# Analog_Filter.net
KiCad netlist of a schematic drawn in Altium Designer
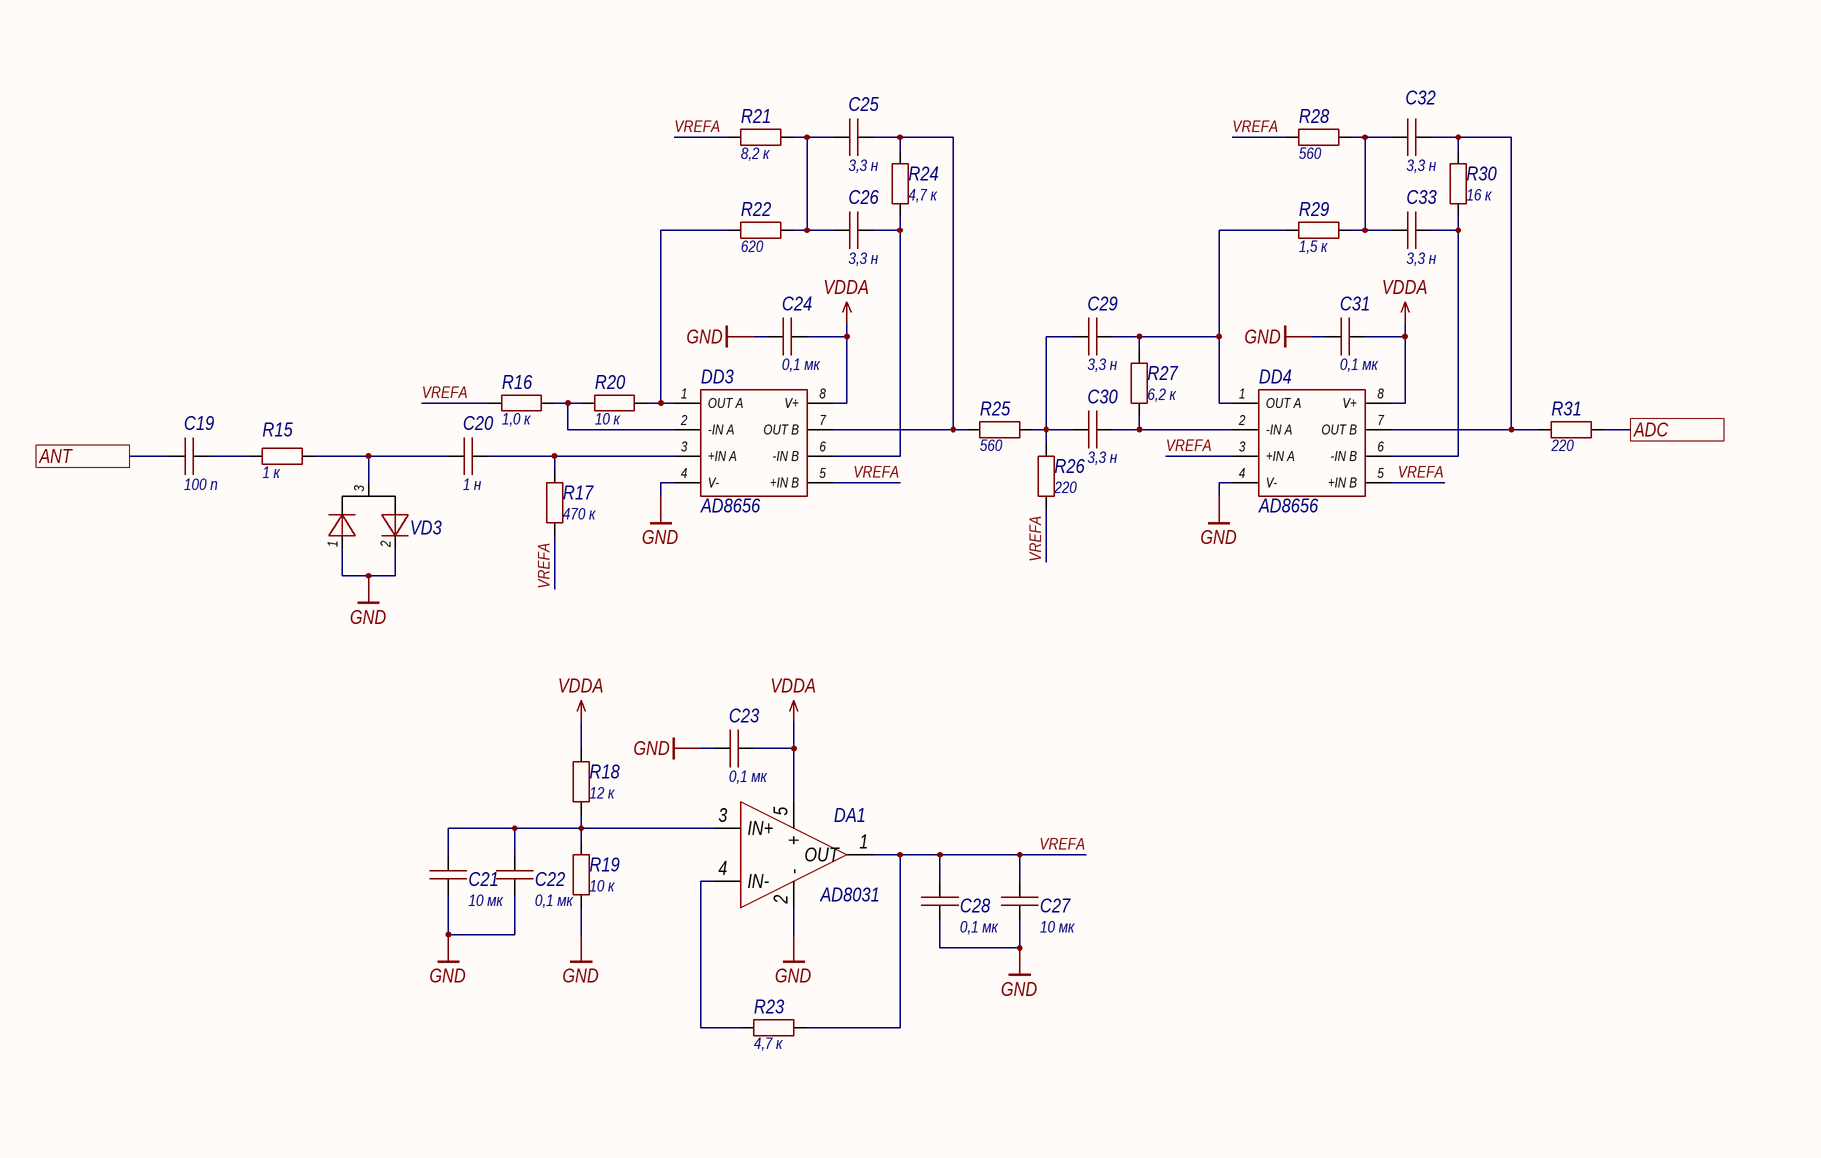
[diagram p0: Analog_Filter.SchDoc, left]
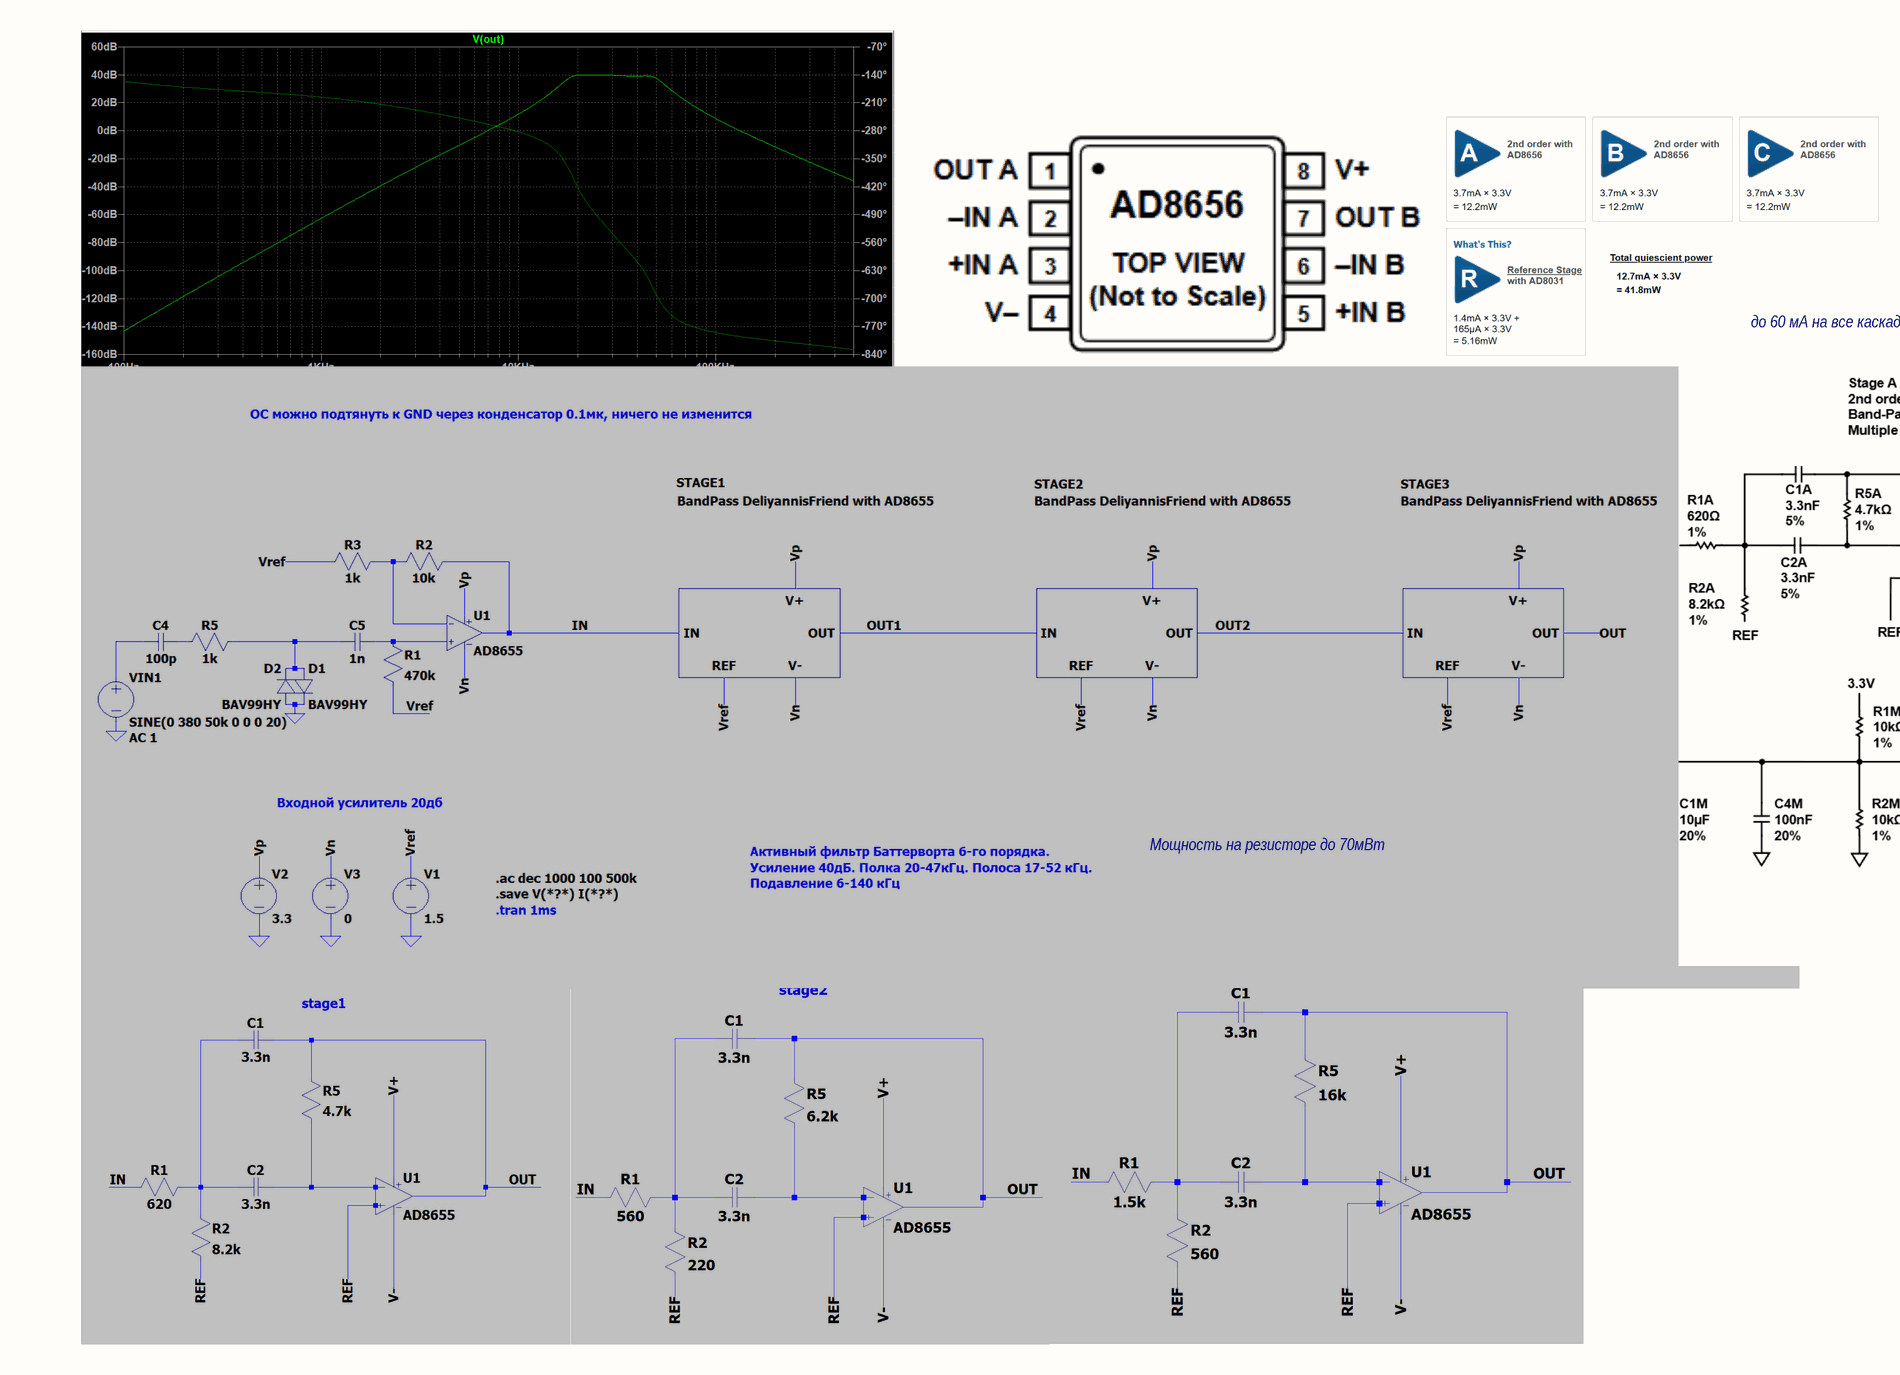
[diagram p1: Analog_Filter.SchDoc, middle]
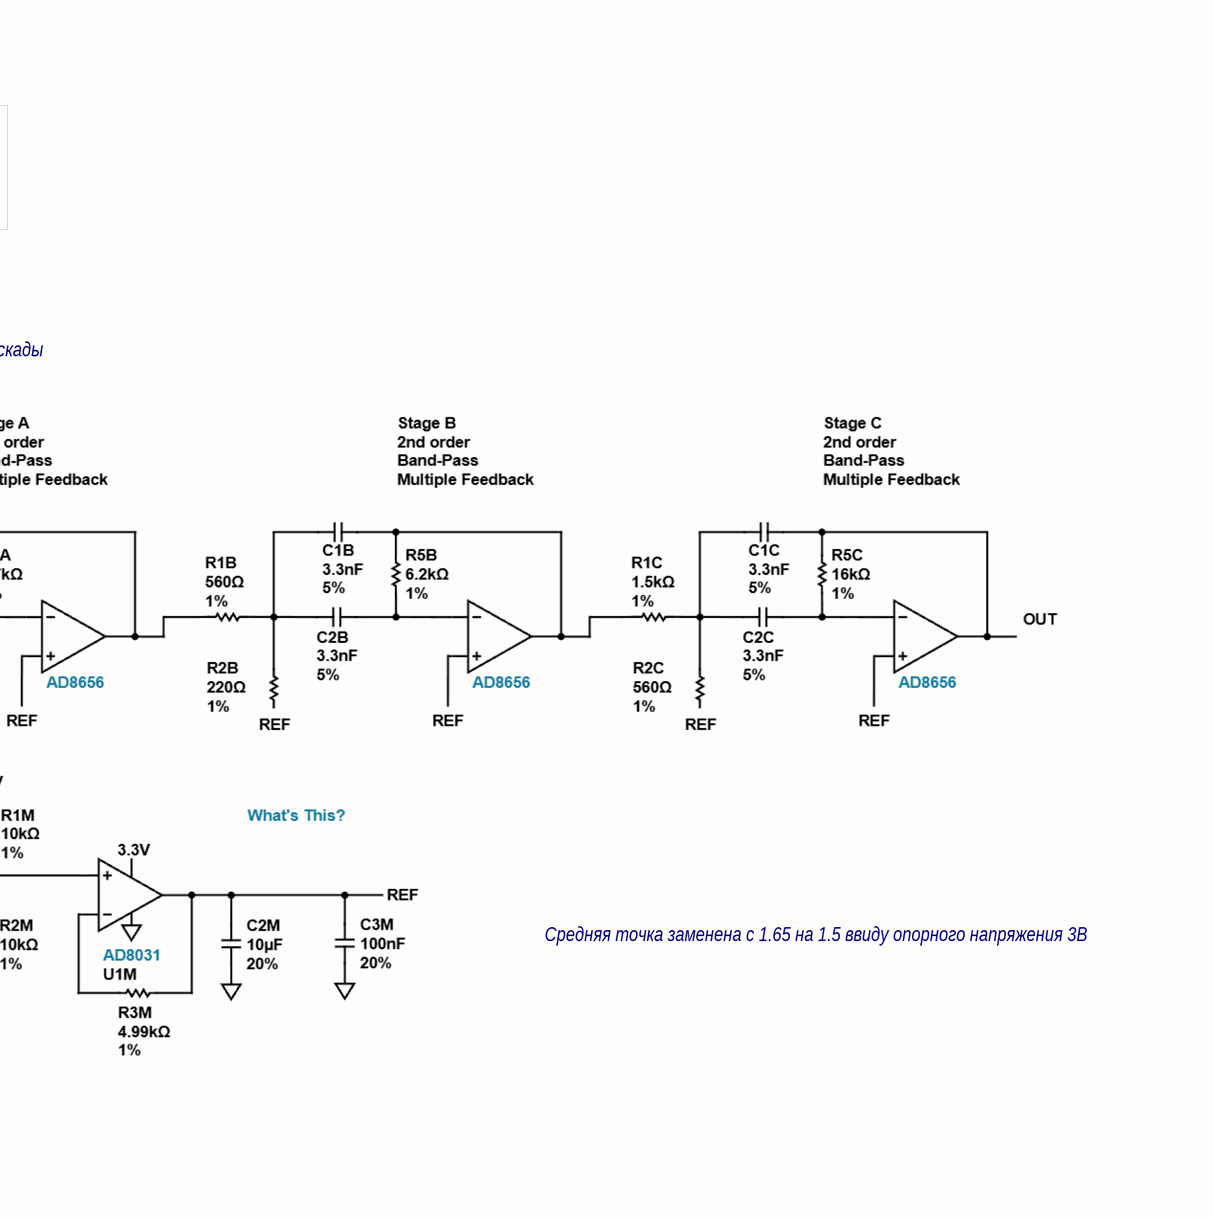
[diagram p2: Analog_Filter.SchDoc, right]

(export (version "E")
  (design (tool "Eeschema 10.0.6"))
  (components
    (comp (ref "C19")
      (value "100 п")
      (footprint "1206C")
      (description "Конденсатор 1206C ёмкостью 100 п 5%, 630 В, NP0")
      (fields
        (field (name "PART NUMBER") "Capacitor_100p_5_630V_NP0_1206C")
        (field (name "TOLERANCE") "5%")
        (field (name "АВТОР") "glebmih")
      )
      (libsource (lib "Hydrolib") (part "Capacitor"))
    )
    (comp (ref "C20")
      (value "1 н")
      (footprint "0603C")
      (description "Конденсатор 0603C ёмкостью 1 н 5%, 50 В, NP0")
      (fields
        (field (name "PART NUMBER") "Capacitor_1n_5_50V_NP0_0603C")
        (field (name "TOLERANCE") "5%")
        (field (name "АВТОР") "glebmih")
      )
      (libsource (lib "Hydrolib") (part "Capacitor"))
    )
    (comp (ref "C21")
      (value "10 мк")
      (footprint "0603C")
      (description "Конденсатор 0603C ёмкостью 10 мк 10%, 10 В, X7R")
      (fields
        (field (name "PART NUMBER") "Capacitor_10u_10_10V_X7R_0603C")
        (field (name "TOLERANCE") "10%")
        (field (name "АВТОР") "glebmih")
      )
      (libsource (lib "Hydrolib") (part "Capacitor"))
    )
    (comp (ref "C22")
      (value "0,1 мк")
      (footprint "0603C")
      (description "Конденсатор 0603C ёмкостью 0,1 мк 10%, 50 В, X7R")
      (fields (field (name "PART NUMBER") "Capacitor_0,1u_10_50V_X7R_0603C") (field (name "TOLERANCE") "10%"))
      (libsource (lib "Hydrolib") (part "Capacitor"))
    )
    (comp (ref "C23")
      (value "0,1 мк")
      (footprint "0603C")
      (description "Конденсатор 0603C ёмкостью 0,1 мк 10%, 50 В, X7R")
      (fields (field (name "PART NUMBER") "Capacitor_0,1u_10_50V_X7R_0603C") (field (name "TOLERANCE") "10%"))
      (libsource (lib "Hydrolib") (part "Capacitor"))
    )
    (comp (ref "C24")
      (value "0,1 мк")
      (footprint "0603C")
      (description "Конденсатор 0603C ёмкостью 0,1 мк 10%, 50 В, X7R")
      (fields (field (name "PART NUMBER") "Capacitor_0,1u_10_50V_X7R_0603C") (field (name "TOLERANCE") "10%"))
      (libsource (lib "Hydrolib") (part "Capacitor"))
    )
    (comp (ref "C25")
      (value "3,3 н")
      (footprint "0603C")
      (description "Конденсатор 0603C ёмкостью 3,3 н 5%, 50 В, NP0")
      (fields
        (field (name "PART NUMBER") "Capacitor_3.3n_5_50V_NP0_0603C")
        (field (name "TOLERANCE") "5%")
        (field (name "АВТОР") "glebmih")
      )
      (libsource (lib "Hydrolib") (part "Capacitor"))
    )
    (comp (ref "C26")
      (value "3,3 н")
      (footprint "0603C")
      (description "Конденсатор 0603C ёмкостью 3,3 н 5%, 50 В, NP0")
      (fields
        (field (name "PART NUMBER") "Capacitor_3.3n_5_50V_NP0_0603C")
        (field (name "TOLERANCE") "5%")
        (field (name "АВТОР") "glebmih")
      )
      (libsource (lib "Hydrolib") (part "Capacitor"))
    )
    (comp (ref "C27")
      (value "10 мк")
      (footprint "0603C")
      (description "Конденсатор 0603C ёмкостью 10 мк 10%, 10 В, X7R")
      (fields
        (field (name "PART NUMBER") "Capacitor_10u_10_10V_X7R_0603C")
        (field (name "TOLERANCE") "10%")
        (field (name "АВТОР") "glebmih")
      )
      (libsource (lib "Hydrolib") (part "Capacitor"))
    )
    (comp (ref "C28")
      (value "0,1 мк")
      (footprint "0603C")
      (description "Конденсатор 0603C ёмкостью 0,1 мк 10%, 50 В, X7R")
      (fields (field (name "PART NUMBER") "Capacitor_0,1u_10_50V_X7R_0603C") (field (name "TOLERANCE") "10%"))
      (libsource (lib "Hydrolib") (part "Capacitor"))
    )
    (comp (ref "C29")
      (value "3,3 н")
      (footprint "0603C")
      (description "Конденсатор 0603C ёмкостью 3,3 н 5%, 50 В, NP0")
      (fields
        (field (name "PART NUMBER") "Capacitor_3.3n_5_50V_NP0_0603C")
        (field (name "TOLERANCE") "5%")
        (field (name "АВТОР") "glebmih")
      )
      (libsource (lib "Hydrolib") (part "Capacitor"))
    )
    (comp (ref "C30")
      (value "3,3 н")
      (footprint "0603C")
      (description "Конденсатор 0603C ёмкостью 3,3 н 5%, 50 В, NP0")
      (fields
        (field (name "PART NUMBER") "Capacitor_3.3n_5_50V_NP0_0603C")
        (field (name "TOLERANCE") "5%")
        (field (name "АВТОР") "glebmih")
      )
      (libsource (lib "Hydrolib") (part "Capacitor"))
    )
    (comp (ref "C31")
      (value "0,1 мк")
      (footprint "0603C")
      (description "Конденсатор 0603C ёмкостью 0,1 мк 10%, 50 В, X7R")
      (fields (field (name "PART NUMBER") "Capacitor_0,1u_10_50V_X7R_0603C") (field (name "TOLERANCE") "10%"))
      (libsource (lib "Hydrolib") (part "Capacitor"))
    )
    (comp (ref "C32")
      (value "3,3 н")
      (footprint "0603C")
      (description "Конденсатор 0603C ёмкостью 3,3 н 5%, 50 В, NP0")
      (fields
        (field (name "PART NUMBER") "Capacitor_3.3n_5_50V_NP0_0603C")
        (field (name "TOLERANCE") "5%")
        (field (name "АВТОР") "glebmih")
      )
      (libsource (lib "Hydrolib") (part "Capacitor"))
    )
    (comp (ref "C33")
      (value "3,3 н")
      (footprint "0603C")
      (description "Конденсатор 0603C ёмкостью 3,3 н 5%, 50 В, NP0")
      (fields
        (field (name "PART NUMBER") "Capacitor_3.3n_5_50V_NP0_0603C")
        (field (name "TOLERANCE") "5%")
        (field (name "АВТОР") "glebmih")
      )
      (libsource (lib "Hydrolib") (part "Capacitor"))
    )
    (comp (ref "DA1")
      (value "AD8031")
      (footprint "SOT23-5")
      (description "Операционный усилитель, 80МГц, 1-канал, 35В/мкс, Voltage Feedback, Rail-to-Rail")
      (fields (field (name "АВТОР") "glebmih"))
      (libsource (lib "Hydrolib") (part "AD8031"))
    )
    (comp (ref "DD3")
      (value "AD8656")
      (footprint "SOIC-8")
      (description "Операционный усилитель 28МГц, CMOS, 2-канала, Rail-to-Rail")
      (fields (field (name "АВТОР") "glebmih"))
      (libsource (lib "Hydrolib") (part "AD8656"))
    )
    (comp (ref "DD4")
      (value "AD8656")
      (footprint "SOIC-8")
      (description "Операционный усилитель 28МГц, CMOS, 2-канала, Rail-to-Rail")
      (fields (field (name "АВТОР") "glebmih"))
      (libsource (lib "Hydrolib") (part "AD8656"))
    )
    (comp (ref "R15")
      (value "1 к")
      (footprint "0805R")
      (description "Резистор номиналом 1 кОм 1%")
      (fields
        (field (name "PART NUMBER") "Resistor_1k_0805")
        (field (name "TOLERANCE") "1%")
        (field (name "АВТОР") "glebmih")
      )
      (libsource (lib "") (part "Resistor_1"))
    )
    (comp (ref "R16")
      (value "1,0 к")
      (footprint "0603R")
      (description "Резистор номиналом 1,0 кОм 1%")
      (fields (field (name "PART NUMBER") "Resistor_1.0k_1_0603") (field (name "TOLERANCE") "1%"))
      (libsource (lib "") (part "Resistor_1"))
    )
    (comp (ref "R17")
      (value "470 к")
      (footprint "0603R")
      (description "Резистор номиналом 470 кОм 1%")
      (fields (field (name "PART NUMBER") "Resistor_470k_1_0603") (field (name "TOLERANCE") "1%"))
      (libsource (lib "") (part "Resistor_2"))
    )
    (comp (ref "R18")
      (value "12 к")
      (footprint "0603R")
      (description "Резистор номиналом 12 кОм 1%")
      (fields (field (name "PART NUMBER") "Resistor_12k_1_0603") (field (name "TOLERANCE") "1%"))
      (libsource (lib "") (part "Resistor_2"))
    )
    (comp (ref "R19")
      (value "10 к")
      (footprint "0603R")
      (description "Резистор номиналом 10 кОм 1%")
      (fields (field (name "PART NUMBER") "Resistor_10k_1_0603") (field (name "TOLERANCE") "1%"))
      (libsource (lib "") (part "Resistor_2"))
    )
    (comp (ref "R20")
      (value "10 к")
      (footprint "0603R")
      (description "Резистор номиналом 10 кОм 1%")
      (fields (field (name "PART NUMBER") "Resistor_10k_1_0603") (field (name "TOLERANCE") "1%"))
      (libsource (lib "") (part "Resistor_1"))
    )
    (comp (ref "R21")
      (value "8,2 к")
      (footprint "0603R")
      (description "Резистор номиналом 8,2 кОм 1%")
      (fields (field (name "PART NUMBER") "Resistor_8.2k_1_0603") (field (name "TOLERANCE") "1%"))
      (libsource (lib "Hydrolib") (part "Resistor"))
    )
    (comp (ref "R22")
      (value "620")
      (footprint "0603R")
      (description "Резистор номиналом 620 Ом 1%")
      (fields (field (name "PART NUMBER") "Resistor_620_1_0603") (field (name "TOLERANCE") "1%"))
      (libsource (lib "") (part "Resistor_1"))
    )
    (comp (ref "R23")
      (value "4,7 к")
      (footprint "0603R")
      (description "Резистор номиналом 4,7 кОм 1%")
      (fields (field (name "PART NUMBER") "Resistor_4.7k_1_0603") (field (name "TOLERANCE") "1%"))
      (libsource (lib "") (part "Resistor_1"))
    )
    (comp (ref "R24")
      (value "4,7 к")
      (footprint "0603R")
      (description "Резистор номиналом 4,7 кОм 1%")
      (fields (field (name "PART NUMBER") "Resistor_4.7k_1_0603") (field (name "TOLERANCE") "1%"))
      (libsource (lib "") (part "Resistor_3"))
    )
    (comp (ref "R25")
      (value "560")
      (footprint "0603R")
      (description "Резистор номиналом 560 Ом 1%")
      (fields (field (name "PART NUMBER") "Resistor_560_1_0603") (field (name "TOLERANCE") "1%"))
      (libsource (lib "") (part "Resistor_1"))
    )
    (comp (ref "R26")
      (value "220")
      (footprint "0603R")
      (description "Резистор номиналом 220 Ом 1%")
      (fields (field (name "PART NUMBER") "Resistor_220_1_0603") (field (name "TOLERANCE") "1%"))
      (libsource (lib "") (part "Resistor_2"))
    )
    (comp (ref "R27")
      (value "6,2 к")
      (footprint "0603R")
      (description "Резистор номиналом 6,2 кОм 1%")
      (fields (field (name "PART NUMBER") "Resistor_6.2k_1_0603") (field (name "TOLERANCE") "1%"))
      (libsource (lib "") (part "Resistor_2"))
    )
    (comp (ref "R28")
      (value "560")
      (footprint "0603R")
      (description "Резистор номиналом 560 Ом 1%")
      (fields (field (name "PART NUMBER") "Resistor_560_1_0603") (field (name "TOLERANCE") "1%"))
      (libsource (lib "") (part "Resistor_1"))
    )
    (comp (ref "R29")
      (value "1,5 к")
      (footprint "0603R")
      (description "Резистор номиналом 1,5 кОм 1%")
      (fields (field (name "PART NUMBER") "Resistor_1.5k_1_0603") (field (name "TOLERANCE") "1%"))
      (libsource (lib "") (part "Resistor_1"))
    )
    (comp (ref "R30")
      (value "16 к")
      (footprint "0603R")
      (description "Резистор номиналом 16 кОм 1%")
      (fields (field (name "PART NUMBER") "Resistor_16k_1_0603") (field (name "TOLERANCE") "1%"))
      (libsource (lib "") (part "Resistor_2"))
    )
    (comp (ref "R31")
      (value "220")
      (footprint "0603R")
      (description "Резистор номиналом 220 Ом 1%")
      (fields (field (name "PART NUMBER") "Resistor_220_1_0603") (field (name "TOLERANCE") "1%"))
      (libsource (lib "") (part "Resistor_1"))
    )
    (comp (ref "VD3")
      (value "BAV99")
      (footprint "SOT23-3")
      (description "Диод импульсный, 2 х 0.2А, 70В, последовательное включение")
      (fields (field (name "АВТОР") "glebmih"))
      (libsource (lib "Hydrolib") (part "Rectifier_diode_2"))
    )
  )
  (nets
    (net (code "1") (name "/ADC") (class "Default")
      (node (ref "R31") (pin "2") (pinfunction "2_2") (pintype "passive"))
    )
    (net (code "2") (name "/ANT") (class "Default")
      (node (ref "C19") (pin "1") (pinfunction "1_1") (pintype "passive"))
    )
    (net (code "3") (name "/VREFA") (class "Default")
      (node (ref "C27") (pin "2") (pinfunction "2_2") (pintype "passive"))
      (node (ref "C28") (pin "2") (pinfunction "2_2") (pintype "passive"))
      (node (ref "DA1") (pin "1") (pinfunction "OUT_1") (pintype "passive"))
      (node (ref "DD3") (pin "5") (pinfunction "+IN_B_5") (pintype "passive"))
      (node (ref "DD4") (pin "3") (pinfunction "+IN_A_3") (pintype "passive"))
      (node (ref "DD4") (pin "5") (pinfunction "+IN_B_5") (pintype "passive"))
      (node (ref "R16") (pin "1") (pinfunction "1_1") (pintype "passive"))
      (node (ref "R17") (pin "1") (pinfunction "1_1") (pintype "passive"))
      (node (ref "R21") (pin "2") (pinfunction "2_2") (pintype "passive"))
      (node (ref "R23") (pin "2") (pinfunction "2_2") (pintype "passive"))
      (node (ref "R26") (pin "1") (pinfunction "1_1") (pintype "passive"))
      (node (ref "R28") (pin "1") (pinfunction "1_1") (pintype "passive"))
    )
    (net (code "4") (name "GND") (class "Default")
      (node (ref "C21") (pin "1") (pinfunction "1_1") (pintype "passive"))
      (node (ref "C22") (pin "1") (pinfunction "1_1") (pintype "passive"))
      (node (ref "C23") (pin "1") (pinfunction "1_1") (pintype "passive"))
      (node (ref "C24") (pin "1") (pinfunction "1_1") (pintype "passive"))
      (node (ref "C27") (pin "1") (pinfunction "1_1") (pintype "passive"))
      (node (ref "C28") (pin "1") (pinfunction "1_1") (pintype "passive"))
      (node (ref "C31") (pin "1") (pinfunction "1_1") (pintype "passive"))
      (node (ref "DA1") (pin "2") (pinfunction "-_2") (pintype "passive"))
      (node (ref "DD3") (pin "4") (pinfunction "V-_4") (pintype "passive"))
      (node (ref "DD4") (pin "4") (pinfunction "V-_4") (pintype "passive"))
      (node (ref "R19") (pin "1") (pinfunction "1_1") (pintype "passive"))
      (node (ref "VD3") (pin "1") (pinfunction "1_1") (pintype "passive"))
      (node (ref "VD3") (pin "2") (pinfunction "2_2") (pintype "passive"))
    )
    (net (code "5") (name "Net-(C19-Pad2)") (class "Default")
      (node (ref "C19") (pin "2") (pinfunction "2_2") (pintype "passive"))
      (node (ref "R15") (pin "1") (pinfunction "1_1") (pintype "passive"))
    )
    (net (code "6") (name "Net-(C20-Pad1)") (class "Default")
      (node (ref "C20") (pin "1") (pinfunction "1_1") (pintype "passive"))
      (node (ref "R15") (pin "2") (pinfunction "2_2") (pintype "passive"))
      (node (ref "VD3") (pin "3") (pinfunction "3_3") (pintype "passive"))
    )
    (net (code "7") (name "Net-(C25-Pad1)") (class "Default")
      (node (ref "C25") (pin "1") (pinfunction "1_1") (pintype "passive"))
      (node (ref "C26") (pin "1") (pinfunction "1_1") (pintype "passive"))
      (node (ref "R21") (pin "1") (pinfunction "1_1") (pintype "passive"))
      (node (ref "R22") (pin "2") (pinfunction "2_2") (pintype "passive"))
    )
    (net (code "8") (name "Net-(C29-Pad1)") (class "Default")
      (node (ref "C29") (pin "1") (pinfunction "1_1") (pintype "passive"))
      (node (ref "C30") (pin "1") (pinfunction "1_1") (pintype "passive"))
      (node (ref "R25") (pin "2") (pinfunction "2_2") (pintype "passive"))
      (node (ref "R26") (pin "2") (pinfunction "2_2") (pintype "passive"))
    )
    (net (code "9") (name "Net-(C32-Pad1)") (class "Default")
      (node (ref "C32") (pin "1") (pinfunction "1_1") (pintype "passive"))
      (node (ref "C33") (pin "1") (pinfunction "1_1") (pintype "passive"))
      (node (ref "R28") (pin "2") (pinfunction "2_2") (pintype "passive"))
      (node (ref "R29") (pin "2") (pinfunction "2_2") (pintype "passive"))
    )
    (net (code "10") (name "Net-(DA1-IN+)") (class "Default")
      (node (ref "C21") (pin "2") (pinfunction "2_2") (pintype "passive"))
      (node (ref "C22") (pin "2") (pinfunction "2_2") (pintype "passive"))
      (node (ref "DA1") (pin "3") (pinfunction "IN+_3") (pintype "passive"))
      (node (ref "R18") (pin "1") (pinfunction "1_1") (pintype "passive"))
      (node (ref "R19") (pin "2") (pinfunction "2_2") (pintype "passive"))
    )
    (net (code "11") (name "Net-(DA1-IN-)") (class "Default")
      (node (ref "DA1") (pin "4") (pinfunction "IN-_4") (pintype "passive"))
      (node (ref "R23") (pin "1") (pinfunction "1_1") (pintype "passive"))
    )
    (net (code "12") (name "Net-(DD3-+IN_A)") (class "Default")
      (node (ref "C20") (pin "2") (pinfunction "2_2") (pintype "passive"))
      (node (ref "DD3") (pin "3") (pinfunction "+IN_A_3") (pintype "passive"))
      (node (ref "R17") (pin "2") (pinfunction "2_2") (pintype "passive"))
    )
    (net (code "13") (name "Net-(DD3--IN_A)") (class "Default")
      (node (ref "DD3") (pin "2") (pinfunction "-IN_A_2") (pintype "passive"))
      (node (ref "R16") (pin "2") (pinfunction "2_2") (pintype "passive"))
      (node (ref "R20") (pin "1") (pinfunction "1_1") (pintype "passive"))
    )
    (net (code "14") (name "Net-(DD3--IN_B)") (class "Default")
      (node (ref "C26") (pin "2") (pinfunction "2_2") (pintype "passive"))
      (node (ref "DD3") (pin "6") (pinfunction "-IN_B_6") (pintype "passive"))
      (node (ref "R24") (pin "2") (pinfunction "2_2") (pintype "passive"))
    )
    (net (code "15") (name "Net-(DD3-OUT_A)") (class "Default")
      (node (ref "DD3") (pin "1") (pinfunction "OUT_A_1") (pintype "passive"))
      (node (ref "R20") (pin "2") (pinfunction "2_2") (pintype "passive"))
      (node (ref "R22") (pin "1") (pinfunction "1_1") (pintype "passive"))
    )
    (net (code "16") (name "Net-(DD3-OUT_B)") (class "Default")
      (node (ref "C25") (pin "2") (pinfunction "2_2") (pintype "passive"))
      (node (ref "DD3") (pin "7") (pinfunction "OUT_B_7") (pintype "passive"))
      (node (ref "R24") (pin "1") (pinfunction "1_1") (pintype "passive"))
      (node (ref "R25") (pin "1") (pinfunction "1_1") (pintype "passive"))
    )
    (net (code "17") (name "Net-(DD4--IN_A)") (class "Default")
      (node (ref "C30") (pin "2") (pinfunction "2_2") (pintype "passive"))
      (node (ref "DD4") (pin "2") (pinfunction "-IN_A_2") (pintype "passive"))
      (node (ref "R27") (pin "1") (pinfunction "1_1") (pintype "passive"))
    )
    (net (code "18") (name "Net-(DD4--IN_B)") (class "Default")
      (node (ref "C33") (pin "2") (pinfunction "2_2") (pintype "passive"))
      (node (ref "DD4") (pin "6") (pinfunction "-IN_B_6") (pintype "passive"))
      (node (ref "R30") (pin "1") (pinfunction "1_1") (pintype "passive"))
    )
    (net (code "19") (name "Net-(DD4-OUT_A)") (class "Default")
      (node (ref "C29") (pin "2") (pinfunction "2_2") (pintype "passive"))
      (node (ref "DD4") (pin "1") (pinfunction "OUT_A_1") (pintype "passive"))
      (node (ref "R27") (pin "2") (pinfunction "2_2") (pintype "passive"))
      (node (ref "R29") (pin "1") (pinfunction "1_1") (pintype "passive"))
    )
    (net (code "20") (name "Net-(DD4-OUT_B)") (class "Default")
      (node (ref "C32") (pin "2") (pinfunction "2_2") (pintype "passive"))
      (node (ref "DD4") (pin "7") (pinfunction "OUT_B_7") (pintype "passive"))
      (node (ref "R30") (pin "2") (pinfunction "2_2") (pintype "passive"))
      (node (ref "R31") (pin "1") (pinfunction "1_1") (pintype "passive"))
    )
    (net (code "21") (name "VDDA") (class "Default")
      (node (ref "C23") (pin "2") (pinfunction "2_2") (pintype "passive"))
      (node (ref "C24") (pin "2") (pinfunction "2_2") (pintype "passive"))
      (node (ref "C31") (pin "2") (pinfunction "2_2") (pintype "passive"))
      (node (ref "DA1") (pin "5") (pinfunction "+_5") (pintype "passive"))
      (node (ref "DD3") (pin "8") (pinfunction "V+_8") (pintype "passive"))
      (node (ref "DD4") (pin "8") (pinfunction "V+_8") (pintype "passive"))
      (node (ref "R18") (pin "2") (pinfunction "2_2") (pintype "passive"))
    )
  )
)
